# Adafruit_HaD_Proto_HAT_rev_A.net
KiCad netlist of a schematic drawn in EAGLE
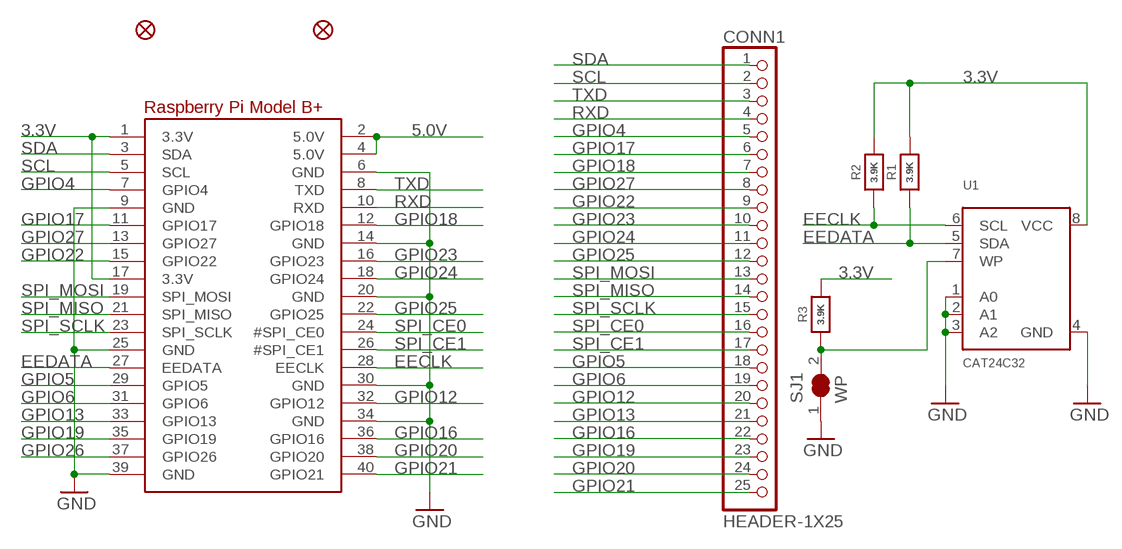
[diagram p0: schematic, sheet 1]

(export (version "E")
  (design (tool "Eeschema 10.0.6"))
  (components
    (comp (ref "CONN1")
      (value "HEADER-1X25")
      (footprint "eagle-import:1X25_ROUND_70MIL")
      (libsource (lib "eagle-import") (part "HEADER-1X25"))
    )
    (comp (ref "FID2")
      (value "FIDUCIAL\"\"")
      (footprint "eagle-import:FIDUCIAL_1MM")
      (libsource (lib "eagle-import") (part "FIDUCIAL{dblquote}{dblquote}"))
    )
    (comp (ref "FID3")
      (value "FIDUCIAL\"\"")
      (footprint "eagle-import:FIDUCIAL_1MM")
      (libsource (lib "eagle-import") (part "FIDUCIAL{dblquote}{dblquote}"))
    )
    (comp (ref "R1")
      (value "3.9K")
      (footprint "eagle-import:0805-NO")
      (libsource (lib "eagle-import") (part "RESISTOR0805_NOOUTLINE"))
    )
    (comp (ref "R2")
      (value "3.9K")
      (footprint "eagle-import:0805-NO")
      (libsource (lib "eagle-import") (part "RESISTOR0805_NOOUTLINE"))
    )
    (comp (ref "R3")
      (value "3.9K")
      (footprint "eagle-import:0805-NO")
      (libsource (lib "eagle-import") (part "RESISTOR0805_NOOUTLINE"))
    )
    (comp (ref "RPI1")
      (value "RASPBERRYPI_BPLUS_HATNOSLOTS")
      (footprint "eagle-import:PI_HAT_NOSLOTS")
      (libsource (lib "eagle-import") (part "RASPBERRYPI_BPLUS_HATNOSLOTS"))
    )
    (comp (ref "SJ1")
      (value "WP")
      (footprint "eagle-import:SOLDERJUMPER_CLOSEDWIRE")
      (libsource (lib "eagle-import") (part "SOLDERJUMPER_CLOSED"))
    )
    (comp (ref "U1")
      (value "CAT24C32")
      (footprint "eagle-import:SOIC8_150MIL")
      (libsource (lib "eagle-import") (part "EEPROM_I2C_SOIC8_GENERIC"))
    )
  )
  (nets
    (net (code "1") (name "/3.3V") (class "Default")
      (node (ref "R1") (pin "2") (pinfunction "2_2") (pintype "passive"))
      (node (ref "R2") (pin "2") (pinfunction "2_2") (pintype "passive"))
      (node (ref "R3") (pin "2") (pinfunction "2_2") (pintype "passive"))
      (node (ref "RPI1") (pin "1") (pinfunction "3.3V_1") (pintype "power_in"))
      (node (ref "RPI1") (pin "17") (pinfunction "3.3V_17") (pintype "power_in"))
      (node (ref "U1") (pin "8") (pinfunction "VCC_8") (pintype "power_in"))
    )
    (net (code "2") (name "/5.0V") (class "Default")
      (node (ref "RPI1") (pin "2") (pinfunction "5.0V_2") (pintype "power_in"))
      (node (ref "RPI1") (pin "4") (pinfunction "5.0V_4") (pintype "power_in"))
    )
    (net (code "3") (name "/EECLK") (class "Default")
      (node (ref "R2") (pin "1") (pinfunction "1_1") (pintype "passive"))
      (node (ref "RPI1") (pin "28") (pinfunction "EECLK_28") (pintype "power_in"))
      (node (ref "U1") (pin "6") (pinfunction "SCL_6") (pintype "input"))
    )
    (net (code "4") (name "/EEDATA") (class "Default")
      (node (ref "R1") (pin "1") (pinfunction "1_1") (pintype "passive"))
      (node (ref "RPI1") (pin "27") (pinfunction "EEDATA_27") (pintype "bidirectional"))
      (node (ref "U1") (pin "5") (pinfunction "SDA_5") (pintype "bidirectional"))
    )
    (net (code "5") (name "/GPIO4") (class "Default")
      (node (ref "CONN1") (pin "5") (pinfunction "5_5") (pintype "passive"))
      (node (ref "RPI1") (pin "7") (pinfunction "GPIO4_7") (pintype "bidirectional"))
    )
    (net (code "6") (name "/GPIO5") (class "Default")
      (node (ref "CONN1") (pin "18") (pinfunction "18_18") (pintype "passive"))
      (node (ref "RPI1") (pin "29") (pinfunction "GPIO5_29") (pintype "bidirectional"))
    )
    (net (code "7") (name "/GPIO6") (class "Default")
      (node (ref "CONN1") (pin "19") (pinfunction "19_19") (pintype "passive"))
      (node (ref "RPI1") (pin "31") (pinfunction "GPIO6_31") (pintype "power_in"))
    )
    (net (code "8") (name "/GPIO12") (class "Default")
      (node (ref "CONN1") (pin "20") (pinfunction "20_20") (pintype "passive"))
      (node (ref "RPI1") (pin "32") (pinfunction "GPIO12_32") (pintype "bidirectional"))
    )
    (net (code "9") (name "/GPIO13") (class "Default")
      (node (ref "CONN1") (pin "21") (pinfunction "21_21") (pintype "passive"))
      (node (ref "RPI1") (pin "33") (pinfunction "GPIO13_33") (pintype "bidirectional"))
    )
    (net (code "10") (name "/GPIO16") (class "Default")
      (node (ref "CONN1") (pin "22") (pinfunction "22_22") (pintype "passive"))
      (node (ref "RPI1") (pin "36") (pinfunction "GPIO16_36") (pintype "power_in"))
    )
    (net (code "11") (name "/GPIO17") (class "Default")
      (node (ref "CONN1") (pin "6") (pinfunction "6_6") (pintype "passive"))
      (node (ref "RPI1") (pin "11") (pinfunction "GPIO17_11") (pintype "bidirectional"))
    )
    (net (code "12") (name "/GPIO18") (class "Default")
      (node (ref "CONN1") (pin "7") (pinfunction "7_7") (pintype "passive"))
      (node (ref "RPI1") (pin "12") (pinfunction "GPIO18_12") (pintype "bidirectional"))
    )
    (net (code "13") (name "/GPIO19") (class "Default")
      (node (ref "CONN1") (pin "23") (pinfunction "23_23") (pintype "passive"))
      (node (ref "RPI1") (pin "35") (pinfunction "GPIO19_35") (pintype "bidirectional"))
    )
    (net (code "14") (name "/GPIO20") (class "Default")
      (node (ref "CONN1") (pin "24") (pinfunction "24_24") (pintype "passive"))
      (node (ref "RPI1") (pin "38") (pinfunction "GPIO20_38") (pintype "bidirectional"))
    )
    (net (code "15") (name "/GPIO21") (class "Default")
      (node (ref "CONN1") (pin "25") (pinfunction "25_25") (pintype "passive"))
      (node (ref "RPI1") (pin "40") (pinfunction "GPIO21_40") (pintype "bidirectional"))
    )
    (net (code "16") (name "/GPIO22") (class "Default")
      (node (ref "CONN1") (pin "9") (pinfunction "9_9") (pintype "passive"))
      (node (ref "RPI1") (pin "15") (pinfunction "GPIO22_15") (pintype "bidirectional"))
    )
    (net (code "17") (name "/GPIO23") (class "Default")
      (node (ref "CONN1") (pin "10") (pinfunction "10_10") (pintype "passive"))
      (node (ref "RPI1") (pin "16") (pinfunction "GPIO23_16") (pintype "bidirectional"))
    )
    (net (code "18") (name "/GPIO24") (class "Default")
      (node (ref "CONN1") (pin "11") (pinfunction "11_11") (pintype "passive"))
      (node (ref "RPI1") (pin "18") (pinfunction "GPIO24_18") (pintype "bidirectional"))
    )
    (net (code "19") (name "/GPIO25") (class "Default")
      (node (ref "CONN1") (pin "12") (pinfunction "12_12") (pintype "passive"))
      (node (ref "RPI1") (pin "22") (pinfunction "GPIO25_22") (pintype "bidirectional"))
    )
    (net (code "20") (name "/GPIO26") (class "Default")
      (node (ref "RPI1") (pin "37") (pinfunction "GPIO26_37") (pintype "bidirectional"))
    )
    (net (code "21") (name "/GPIO27") (class "Default")
      (node (ref "CONN1") (pin "8") (pinfunction "8_8") (pintype "passive"))
      (node (ref "RPI1") (pin "13") (pinfunction "GPIO27_13") (pintype "bidirectional"))
    )
    (net (code "22") (name "/RXD") (class "Default")
      (node (ref "CONN1") (pin "4") (pinfunction "4_4") (pintype "passive"))
      (node (ref "RPI1") (pin "10") (pinfunction "RXD_10") (pintype "bidirectional"))
    )
    (net (code "23") (name "/SCL") (class "Default")
      (node (ref "CONN1") (pin "2") (pinfunction "2_2") (pintype "passive"))
      (node (ref "RPI1") (pin "5") (pinfunction "SCL_5") (pintype "bidirectional"))
    )
    (net (code "24") (name "/SDA") (class "Default")
      (node (ref "CONN1") (pin "1") (pinfunction "1_1") (pintype "passive"))
      (node (ref "RPI1") (pin "3") (pinfunction "SDA_3") (pintype "bidirectional"))
    )
    (net (code "25") (name "/SPI_CE0") (class "Default")
      (node (ref "CONN1") (pin "16") (pinfunction "16_16") (pintype "passive"))
      (node (ref "RPI1") (pin "24") (pinfunction "#SPI_CE0_24") (pintype "bidirectional"))
    )
    (net (code "26") (name "/SPI_CE1") (class "Default")
      (node (ref "CONN1") (pin "17") (pinfunction "17_17") (pintype "passive"))
      (node (ref "RPI1") (pin "26") (pinfunction "#SPI_CE1_26") (pintype "bidirectional"))
    )
    (net (code "27") (name "/SPI_MISO") (class "Default")
      (node (ref "CONN1") (pin "14") (pinfunction "14_14") (pintype "passive"))
      (node (ref "RPI1") (pin "21") (pinfunction "SPI_MISO_21") (pintype "bidirectional"))
    )
    (net (code "28") (name "/SPI_MOSI") (class "Default")
      (node (ref "CONN1") (pin "13") (pinfunction "13_13") (pintype "passive"))
      (node (ref "RPI1") (pin "19") (pinfunction "SPI_MOSI_19") (pintype "bidirectional"))
    )
    (net (code "29") (name "/SPI_SCLK") (class "Default")
      (node (ref "CONN1") (pin "15") (pinfunction "15_15") (pintype "passive"))
      (node (ref "RPI1") (pin "23") (pinfunction "SPI_SCLK_23") (pintype "bidirectional"))
    )
    (net (code "30") (name "/TXD") (class "Default")
      (node (ref "CONN1") (pin "3") (pinfunction "3_3") (pintype "passive"))
      (node (ref "RPI1") (pin "8") (pinfunction "TXD_8") (pintype "output"))
    )
    (net (code "31") (name "GND") (class "Default")
      (node (ref "RPI1") (pin "14") (pinfunction "GND_14") (pintype "power_in"))
      (node (ref "RPI1") (pin "20") (pinfunction "GND_20") (pintype "power_in"))
      (node (ref "RPI1") (pin "25") (pinfunction "GND_25") (pintype "power_in"))
      (node (ref "RPI1") (pin "30") (pinfunction "GND_30") (pintype "bidirectional"))
      (node (ref "RPI1") (pin "34") (pinfunction "GND_34") (pintype "bidirectional"))
      (node (ref "RPI1") (pin "39") (pinfunction "GND_39") (pintype "power_in"))
      (node (ref "RPI1") (pin "6") (pinfunction "GND_6") (pintype "power_in"))
      (node (ref "RPI1") (pin "9") (pinfunction "GND_9") (pintype "power_in"))
      (node (ref "SJ1") (pin "1") (pinfunction "1_1") (pintype "passive"))
      (node (ref "U1") (pin "1") (pinfunction "A0_1") (pintype "input"))
      (node (ref "U1") (pin "2") (pinfunction "A1_2") (pintype "input"))
      (node (ref "U1") (pin "3") (pinfunction "A2_3") (pintype "input"))
      (node (ref "U1") (pin "4") (pinfunction "GND_4") (pintype "power_in"))
    )
    (net (code "32") (name "Net-(U1-WP)") (class "Default")
      (node (ref "R3") (pin "1") (pinfunction "1_1") (pintype "passive"))
      (node (ref "SJ1") (pin "2") (pinfunction "2_2") (pintype "passive"))
      (node (ref "U1") (pin "7") (pinfunction "WP_7") (pintype "input"))
    )
  )
)
